# W002B.net
KiCad netlist of a schematic drawn in EAGLE
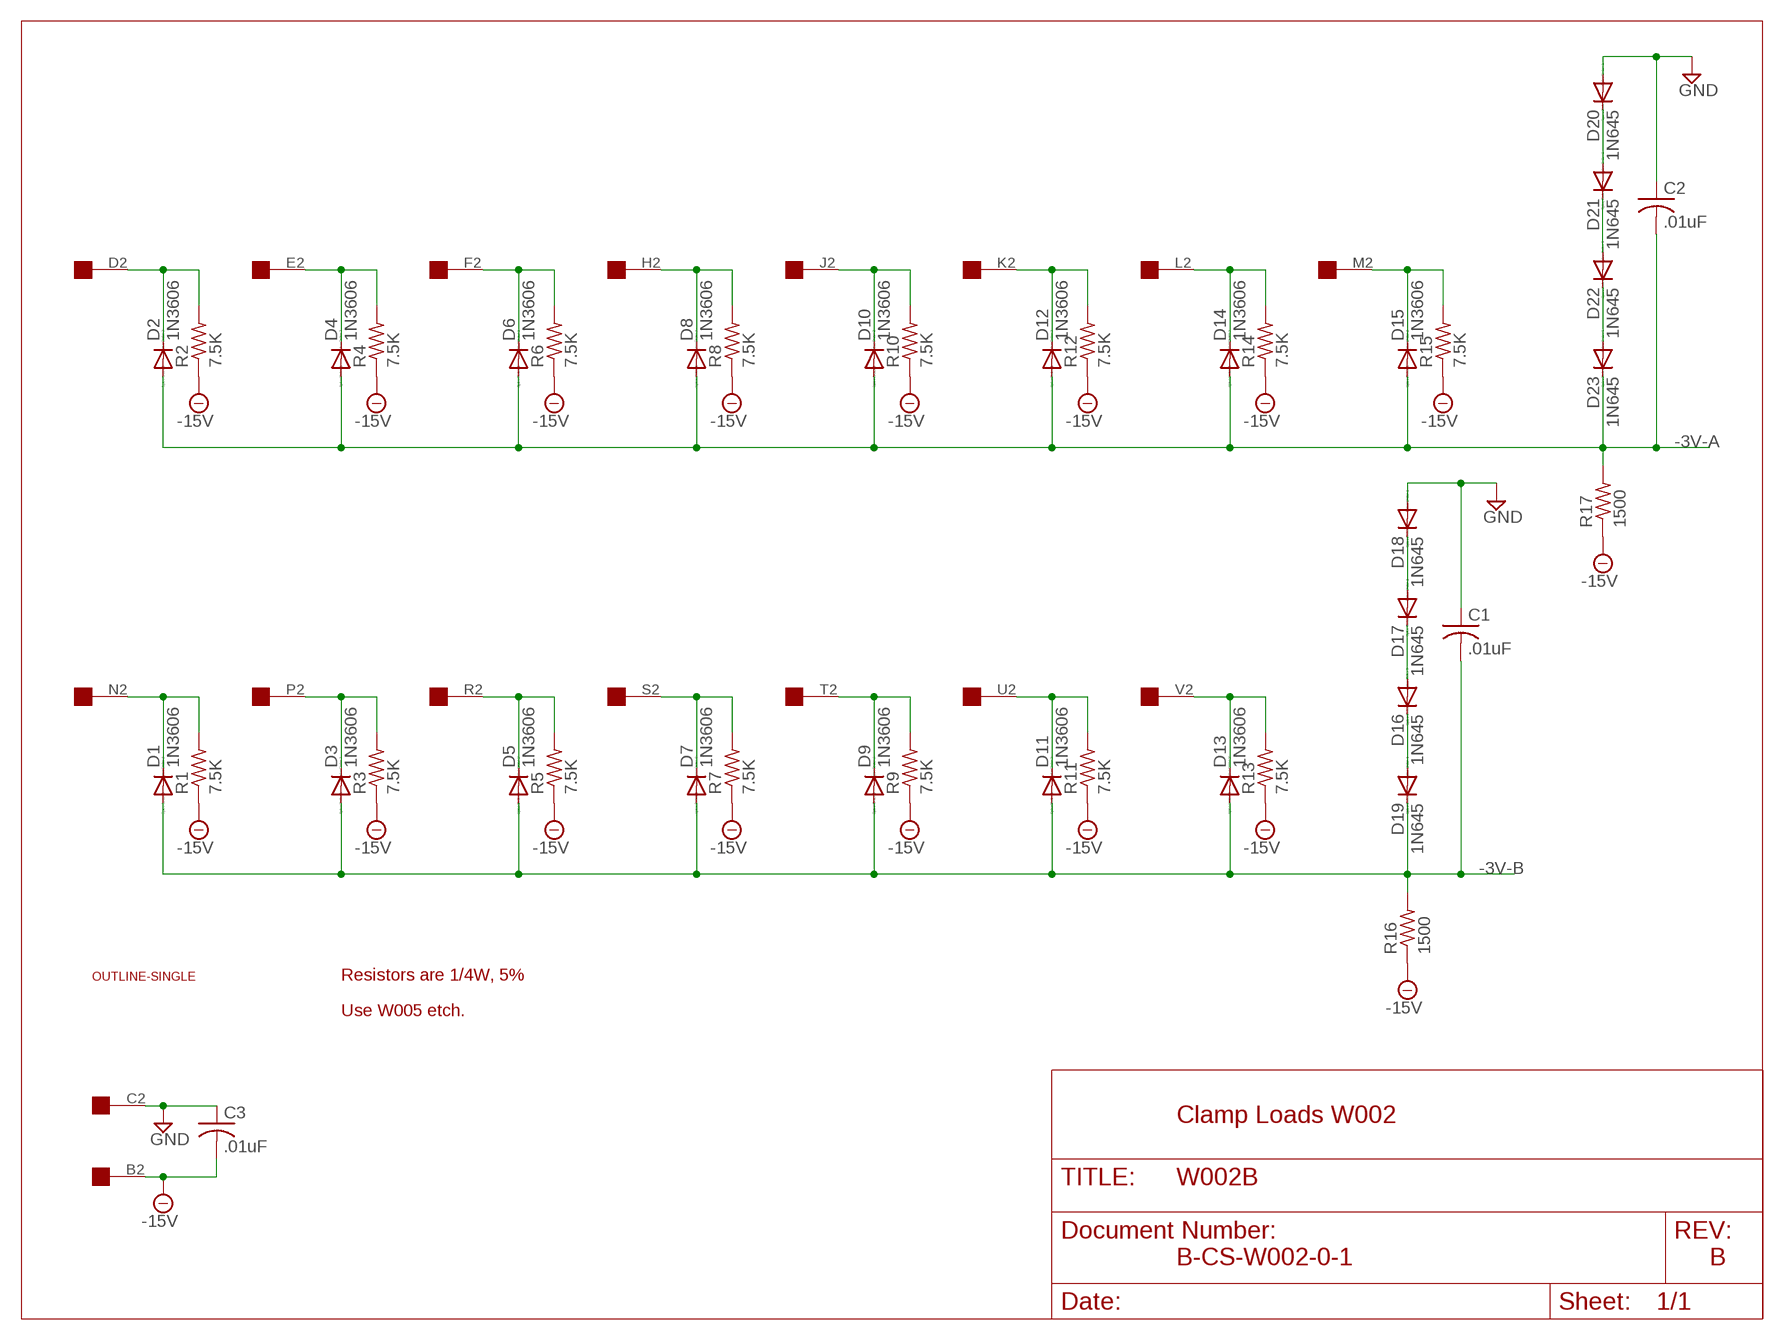
[diagram p0: schematic, sheet 1]

(export (version "E")
  (design (tool "Eeschema 10.0.6"))
  (components
    (comp (ref "C1")
      (value ".01uF")
      (footprint "eagle-import:C050-025X075")
      (libsource (lib "eagle-import") (part "C-US050-025X075"))
    )
    (comp (ref "C2")
      (value ".01uF")
      (footprint "eagle-import:C050-025X075")
      (libsource (lib "eagle-import") (part "C-US050-025X075"))
    )
    (comp (ref "C3")
      (value ".01uF")
      (footprint "eagle-import:C050-025X075")
      (libsource (lib "eagle-import") (part "C-US050-025X075"))
    )
    (comp (ref "D1")
      (value "1N3606")
      (footprint "eagle-import:DO35-10")
      (libsource (lib "eagle-import") (part "1N4148DO35-10"))
    )
    (comp (ref "D2")
      (value "1N3606")
      (footprint "eagle-import:DO35-10")
      (libsource (lib "eagle-import") (part "1N4148DO35-10"))
    )
    (comp (ref "D3")
      (value "1N3606")
      (footprint "eagle-import:DO35-10")
      (libsource (lib "eagle-import") (part "1N4148DO35-10"))
    )
    (comp (ref "D4")
      (value "1N3606")
      (footprint "eagle-import:DO35-10")
      (libsource (lib "eagle-import") (part "1N4148DO35-10"))
    )
    (comp (ref "D5")
      (value "1N3606")
      (footprint "eagle-import:DO35-10")
      (libsource (lib "eagle-import") (part "1N4148DO35-10"))
    )
    (comp (ref "D6")
      (value "1N3606")
      (footprint "eagle-import:DO35-10")
      (libsource (lib "eagle-import") (part "1N4148DO35-10"))
    )
    (comp (ref "D7")
      (value "1N3606")
      (footprint "eagle-import:DO35-10")
      (libsource (lib "eagle-import") (part "1N4148DO35-10"))
    )
    (comp (ref "D8")
      (value "1N3606")
      (footprint "eagle-import:DO35-10")
      (libsource (lib "eagle-import") (part "1N4148DO35-10"))
    )
    (comp (ref "D9")
      (value "1N3606")
      (footprint "eagle-import:DO35-10")
      (libsource (lib "eagle-import") (part "1N4148DO35-10"))
    )
    (comp (ref "D10")
      (value "1N3606")
      (footprint "eagle-import:DO35-10")
      (libsource (lib "eagle-import") (part "1N4148DO35-10"))
    )
    (comp (ref "D11")
      (value "1N3606")
      (footprint "eagle-import:DO35-10")
      (libsource (lib "eagle-import") (part "1N4148DO35-10"))
    )
    (comp (ref "D12")
      (value "1N3606")
      (footprint "eagle-import:DO35-10")
      (libsource (lib "eagle-import") (part "1N4148DO35-10"))
    )
    (comp (ref "D13")
      (value "1N3606")
      (footprint "eagle-import:DO35-10")
      (libsource (lib "eagle-import") (part "1N4148DO35-10"))
    )
    (comp (ref "D14")
      (value "1N3606")
      (footprint "eagle-import:DO35-10")
      (libsource (lib "eagle-import") (part "1N4148DO35-10"))
    )
    (comp (ref "D15")
      (value "1N3606")
      (footprint "eagle-import:DO35-10")
      (libsource (lib "eagle-import") (part "1N4148DO35-10"))
    )
    (comp (ref "D16")
      (value "1N645")
      (footprint "eagle-import:DO35-10")
      (libsource (lib "eagle-import") (part "1N4148DO35-10"))
    )
    (comp (ref "D17")
      (value "1N645")
      (footprint "eagle-import:DO35-10")
      (libsource (lib "eagle-import") (part "1N4148DO35-10"))
    )
    (comp (ref "D18")
      (value "1N645")
      (footprint "eagle-import:DO35-10")
      (libsource (lib "eagle-import") (part "1N4148DO35-10"))
    )
    (comp (ref "D19")
      (value "1N645")
      (footprint "eagle-import:DO35-10")
      (libsource (lib "eagle-import") (part "1N4148DO35-10"))
    )
    (comp (ref "D20")
      (value "1N645")
      (footprint "eagle-import:DO35-10")
      (libsource (lib "eagle-import") (part "1N4148DO35-10"))
    )
    (comp (ref "D21")
      (value "1N645")
      (footprint "eagle-import:DO35-10")
      (libsource (lib "eagle-import") (part "1N4148DO35-10"))
    )
    (comp (ref "D22")
      (value "1N645")
      (footprint "eagle-import:DO35-10")
      (libsource (lib "eagle-import") (part "1N4148DO35-10"))
    )
    (comp (ref "D23")
      (value "1N645")
      (footprint "eagle-import:DO35-10")
      (libsource (lib "eagle-import") (part "1N4148DO35-10"))
    )
    (comp (ref "R1")
      (value "7.5K")
      (footprint "eagle-import:0207_10")
      (libsource (lib "eagle-import") (part "R-US_0207/10"))
    )
    (comp (ref "R2")
      (value "7.5K")
      (footprint "eagle-import:0207_10")
      (libsource (lib "eagle-import") (part "R-US_0207/10"))
    )
    (comp (ref "R3")
      (value "7.5K")
      (footprint "eagle-import:0207_10")
      (libsource (lib "eagle-import") (part "R-US_0207/10"))
    )
    (comp (ref "R4")
      (value "7.5K")
      (footprint "eagle-import:0207_10")
      (libsource (lib "eagle-import") (part "R-US_0207/10"))
    )
    (comp (ref "R5")
      (value "7.5K")
      (footprint "eagle-import:0207_10")
      (libsource (lib "eagle-import") (part "R-US_0207/10"))
    )
    (comp (ref "R6")
      (value "7.5K")
      (footprint "eagle-import:0207_10")
      (libsource (lib "eagle-import") (part "R-US_0207/10"))
    )
    (comp (ref "R7")
      (value "7.5K")
      (footprint "eagle-import:0207_10")
      (libsource (lib "eagle-import") (part "R-US_0207/10"))
    )
    (comp (ref "R8")
      (value "7.5K")
      (footprint "eagle-import:0207_10")
      (libsource (lib "eagle-import") (part "R-US_0207/10"))
    )
    (comp (ref "R9")
      (value "7.5K")
      (footprint "eagle-import:0207_10")
      (libsource (lib "eagle-import") (part "R-US_0207/10"))
    )
    (comp (ref "R10")
      (value "7.5K")
      (footprint "eagle-import:0207_10")
      (libsource (lib "eagle-import") (part "R-US_0207/10"))
    )
    (comp (ref "R11")
      (value "7.5K")
      (footprint "eagle-import:0207_10")
      (libsource (lib "eagle-import") (part "R-US_0207/10"))
    )
    (comp (ref "R12")
      (value "7.5K")
      (footprint "eagle-import:0207_10")
      (libsource (lib "eagle-import") (part "R-US_0207/10"))
    )
    (comp (ref "R13")
      (value "7.5K")
      (footprint "eagle-import:0207_10")
      (libsource (lib "eagle-import") (part "R-US_0207/10"))
    )
    (comp (ref "R14")
      (value "7.5K")
      (footprint "eagle-import:0207_10")
      (libsource (lib "eagle-import") (part "R-US_0207/10"))
    )
    (comp (ref "R15")
      (value "7.5K")
      (footprint "eagle-import:0207_10")
      (libsource (lib "eagle-import") (part "R-US_0207/10"))
    )
    (comp (ref "R16")
      (value "1500")
      (footprint "eagle-import:0207_10")
      (libsource (lib "eagle-import") (part "R-US_0207/10"))
    )
    (comp (ref "R17")
      (value "1500")
      (footprint "eagle-import:0207_10")
      (libsource (lib "eagle-import") (part "R-US_0207/10"))
    )
    (comp (ref "U$1")
      (value "OUTLINE-SINGLE")
      (footprint "eagle-import:SINGLE")
      (libsource (lib "eagle-import") (part "OUTLINE-SINGLE"))
    )
    (comp (ref "U$2")
      (value "EDGE-1")
      (footprint "eagle-import:EDGE-CON1")
      (libsource (lib "eagle-import") (part "EDGE-1"))
    )
  )
  (nets
    (net (code "1") (name "-15V") (class "Default")
      (node (ref "C3") (pin "2") (pinfunction "2_2") (pintype "passive"))
      (node (ref "R1") (pin "1") (pinfunction "1_1") (pintype "passive"))
      (node (ref "R10") (pin "1") (pinfunction "1_1") (pintype "passive"))
      (node (ref "R11") (pin "1") (pinfunction "1_1") (pintype "passive"))
      (node (ref "R12") (pin "1") (pinfunction "1_1") (pintype "passive"))
      (node (ref "R13") (pin "1") (pinfunction "1_1") (pintype "passive"))
      (node (ref "R14") (pin "1") (pinfunction "1_1") (pintype "passive"))
      (node (ref "R15") (pin "1") (pinfunction "1_1") (pintype "passive"))
      (node (ref "R16") (pin "1") (pinfunction "1_1") (pintype "passive"))
      (node (ref "R17") (pin "1") (pinfunction "1_1") (pintype "passive"))
      (node (ref "R2") (pin "1") (pinfunction "1_1") (pintype "passive"))
      (node (ref "R3") (pin "1") (pinfunction "1_1") (pintype "passive"))
      (node (ref "R4") (pin "1") (pinfunction "1_1") (pintype "passive"))
      (node (ref "R5") (pin "1") (pinfunction "1_1") (pintype "passive"))
      (node (ref "R6") (pin "1") (pinfunction "1_1") (pintype "passive"))
      (node (ref "R7") (pin "1") (pinfunction "1_1") (pintype "passive"))
      (node (ref "R8") (pin "1") (pinfunction "1_1") (pintype "passive"))
      (node (ref "R9") (pin "1") (pinfunction "1_1") (pintype "passive"))
      (node (ref "U$2") (pin "B2") (pinfunction "1_B2") (pintype "bidirectional"))
    )
    (net (code "2") (name "/-3V-A") (class "Default")
      (node (ref "C2") (pin "2") (pinfunction "2_2") (pintype "passive"))
      (node (ref "D10") (pin "A") (pinfunction "A_A") (pintype "passive"))
      (node (ref "D12") (pin "A") (pinfunction "A_A") (pintype "passive"))
      (node (ref "D14") (pin "A") (pinfunction "A_A") (pintype "passive"))
      (node (ref "D15") (pin "A") (pinfunction "A_A") (pintype "passive"))
      (node (ref "D2") (pin "A") (pinfunction "A_A") (pintype "passive"))
      (node (ref "D23") (pin "C") (pinfunction "C_C") (pintype "passive"))
      (node (ref "D4") (pin "A") (pinfunction "A_A") (pintype "passive"))
      (node (ref "D6") (pin "A") (pinfunction "A_A") (pintype "passive"))
      (node (ref "D8") (pin "A") (pinfunction "A_A") (pintype "passive"))
      (node (ref "R17") (pin "2") (pinfunction "2_2") (pintype "passive"))
    )
    (net (code "3") (name "/-3V-B") (class "Default")
      (node (ref "C1") (pin "2") (pinfunction "2_2") (pintype "passive"))
      (node (ref "D1") (pin "A") (pinfunction "A_A") (pintype "passive"))
      (node (ref "D11") (pin "A") (pinfunction "A_A") (pintype "passive"))
      (node (ref "D13") (pin "A") (pinfunction "A_A") (pintype "passive"))
      (node (ref "D19") (pin "C") (pinfunction "C_C") (pintype "passive"))
      (node (ref "D3") (pin "A") (pinfunction "A_A") (pintype "passive"))
      (node (ref "D5") (pin "A") (pinfunction "A_A") (pintype "passive"))
      (node (ref "D7") (pin "A") (pinfunction "A_A") (pintype "passive"))
      (node (ref "D9") (pin "A") (pinfunction "A_A") (pintype "passive"))
      (node (ref "R16") (pin "2") (pinfunction "2_2") (pintype "passive"))
    )
    (net (code "4") (name "GND") (class "Default")
      (node (ref "C1") (pin "1") (pinfunction "1_1") (pintype "passive"))
      (node (ref "C2") (pin "1") (pinfunction "1_1") (pintype "passive"))
      (node (ref "C3") (pin "1") (pinfunction "1_1") (pintype "passive"))
      (node (ref "D18") (pin "A") (pinfunction "A_A") (pintype "passive"))
      (node (ref "D20") (pin "A") (pinfunction "A_A") (pintype "passive"))
      (node (ref "U$2") (pin "C2") (pinfunction "1_C2") (pintype "bidirectional"))
    )
    (net (code "5") (name "Net-(D16-PadA)") (class "Default")
      (node (ref "D16") (pin "A") (pinfunction "A_A") (pintype "passive"))
      (node (ref "D17") (pin "C") (pinfunction "C_C") (pintype "passive"))
    )
    (net (code "6") (name "Net-(D16-PadC)") (class "Default")
      (node (ref "D16") (pin "C") (pinfunction "C_C") (pintype "passive"))
      (node (ref "D19") (pin "A") (pinfunction "A_A") (pintype "passive"))
    )
    (net (code "7") (name "Net-(D17-PadA)") (class "Default")
      (node (ref "D17") (pin "A") (pinfunction "A_A") (pintype "passive"))
      (node (ref "D18") (pin "C") (pinfunction "C_C") (pintype "passive"))
    )
    (net (code "8") (name "Net-(D20-PadC)") (class "Default")
      (node (ref "D20") (pin "C") (pinfunction "C_C") (pintype "passive"))
      (node (ref "D21") (pin "A") (pinfunction "A_A") (pintype "passive"))
    )
    (net (code "9") (name "Net-(D21-PadC)") (class "Default")
      (node (ref "D21") (pin "C") (pinfunction "C_C") (pintype "passive"))
      (node (ref "D22") (pin "A") (pinfunction "A_A") (pintype "passive"))
    )
    (net (code "10") (name "Net-(D22-PadC)") (class "Default")
      (node (ref "D22") (pin "C") (pinfunction "C_C") (pintype "passive"))
      (node (ref "D23") (pin "A") (pinfunction "A_A") (pintype "passive"))
    )
    (net (code "11") (name "Net-(U$2D-1)") (class "Default")
      (node (ref "D2") (pin "C") (pinfunction "C_C") (pintype "passive"))
      (node (ref "R2") (pin "2") (pinfunction "2_2") (pintype "passive"))
      (node (ref "U$2") (pin "D2") (pinfunction "1_D2") (pintype "bidirectional"))
    )
    (net (code "12") (name "Net-(U$2E-1)") (class "Default")
      (node (ref "D4") (pin "C") (pinfunction "C_C") (pintype "passive"))
      (node (ref "R4") (pin "2") (pinfunction "2_2") (pintype "passive"))
      (node (ref "U$2") (pin "E2") (pinfunction "1_E2") (pintype "bidirectional"))
    )
    (net (code "13") (name "Net-(U$2F-1)") (class "Default")
      (node (ref "D6") (pin "C") (pinfunction "C_C") (pintype "passive"))
      (node (ref "R6") (pin "2") (pinfunction "2_2") (pintype "passive"))
      (node (ref "U$2") (pin "F2") (pinfunction "1_F2") (pintype "bidirectional"))
    )
    (net (code "14") (name "Net-(U$2G-1)") (class "Default")
      (node (ref "D8") (pin "C") (pinfunction "C_C") (pintype "passive"))
      (node (ref "R8") (pin "2") (pinfunction "2_2") (pintype "passive"))
      (node (ref "U$2") (pin "H2") (pinfunction "1_H2") (pintype "bidirectional"))
    )
    (net (code "15") (name "Net-(U$2H-1)") (class "Default")
      (node (ref "D10") (pin "C") (pinfunction "C_C") (pintype "passive"))
      (node (ref "R10") (pin "2") (pinfunction "2_2") (pintype "passive"))
      (node (ref "U$2") (pin "J2") (pinfunction "1_J2") (pintype "bidirectional"))
    )
    (net (code "16") (name "Net-(U$2I-1)") (class "Default")
      (node (ref "D12") (pin "C") (pinfunction "C_C") (pintype "passive"))
      (node (ref "R12") (pin "2") (pinfunction "2_2") (pintype "passive"))
      (node (ref "U$2") (pin "K2") (pinfunction "1_K2") (pintype "bidirectional"))
    )
    (net (code "17") (name "Net-(U$2J-1)") (class "Default")
      (node (ref "D14") (pin "C") (pinfunction "C_C") (pintype "passive"))
      (node (ref "R14") (pin "2") (pinfunction "2_2") (pintype "passive"))
      (node (ref "U$2") (pin "L2") (pinfunction "1_L2") (pintype "bidirectional"))
    )
    (net (code "18") (name "Net-(U$2K-1)") (class "Default")
      (node (ref "D15") (pin "C") (pinfunction "C_C") (pintype "passive"))
      (node (ref "R15") (pin "2") (pinfunction "2_2") (pintype "passive"))
      (node (ref "U$2") (pin "M2") (pinfunction "1_M2") (pintype "bidirectional"))
    )
    (net (code "19") (name "Net-(U$2L-1)") (class "Default")
      (node (ref "D1") (pin "C") (pinfunction "C_C") (pintype "passive"))
      (node (ref "R1") (pin "2") (pinfunction "2_2") (pintype "passive"))
      (node (ref "U$2") (pin "N2") (pinfunction "1_N2") (pintype "bidirectional"))
    )
    (net (code "20") (name "Net-(U$2M-1)") (class "Default")
      (node (ref "D3") (pin "C") (pinfunction "C_C") (pintype "passive"))
      (node (ref "R3") (pin "2") (pinfunction "2_2") (pintype "passive"))
      (node (ref "U$2") (pin "P2") (pinfunction "1_P2") (pintype "bidirectional"))
    )
    (net (code "21") (name "Net-(U$2N-1)") (class "Default")
      (node (ref "D5") (pin "C") (pinfunction "C_C") (pintype "passive"))
      (node (ref "R5") (pin "2") (pinfunction "2_2") (pintype "passive"))
      (node (ref "U$2") (pin "R2") (pinfunction "1_R2") (pintype "bidirectional"))
    )
    (net (code "22") (name "Net-(U$2O-1)") (class "Default")
      (node (ref "D7") (pin "C") (pinfunction "C_C") (pintype "passive"))
      (node (ref "R7") (pin "2") (pinfunction "2_2") (pintype "passive"))
      (node (ref "U$2") (pin "S2") (pinfunction "1_S2") (pintype "bidirectional"))
    )
    (net (code "23") (name "Net-(U$2P-1)") (class "Default")
      (node (ref "D9") (pin "C") (pinfunction "C_C") (pintype "passive"))
      (node (ref "R9") (pin "2") (pinfunction "2_2") (pintype "passive"))
      (node (ref "U$2") (pin "T2") (pinfunction "1_T2") (pintype "bidirectional"))
    )
    (net (code "24") (name "Net-(U$2Q-1)") (class "Default")
      (node (ref "D11") (pin "C") (pinfunction "C_C") (pintype "passive"))
      (node (ref "R11") (pin "2") (pinfunction "2_2") (pintype "passive"))
      (node (ref "U$2") (pin "U2") (pinfunction "1_U2") (pintype "bidirectional"))
    )
    (net (code "25") (name "Net-(U$2R-1)") (class "Default")
      (node (ref "D13") (pin "C") (pinfunction "C_C") (pintype "passive"))
      (node (ref "R13") (pin "2") (pinfunction "2_2") (pintype "passive"))
      (node (ref "U$2") (pin "V2") (pinfunction "1_V2") (pintype "bidirectional"))
    )
  )
)
